# WindVane_1.net
KiCad netlist of a schematic drawn in EAGLE
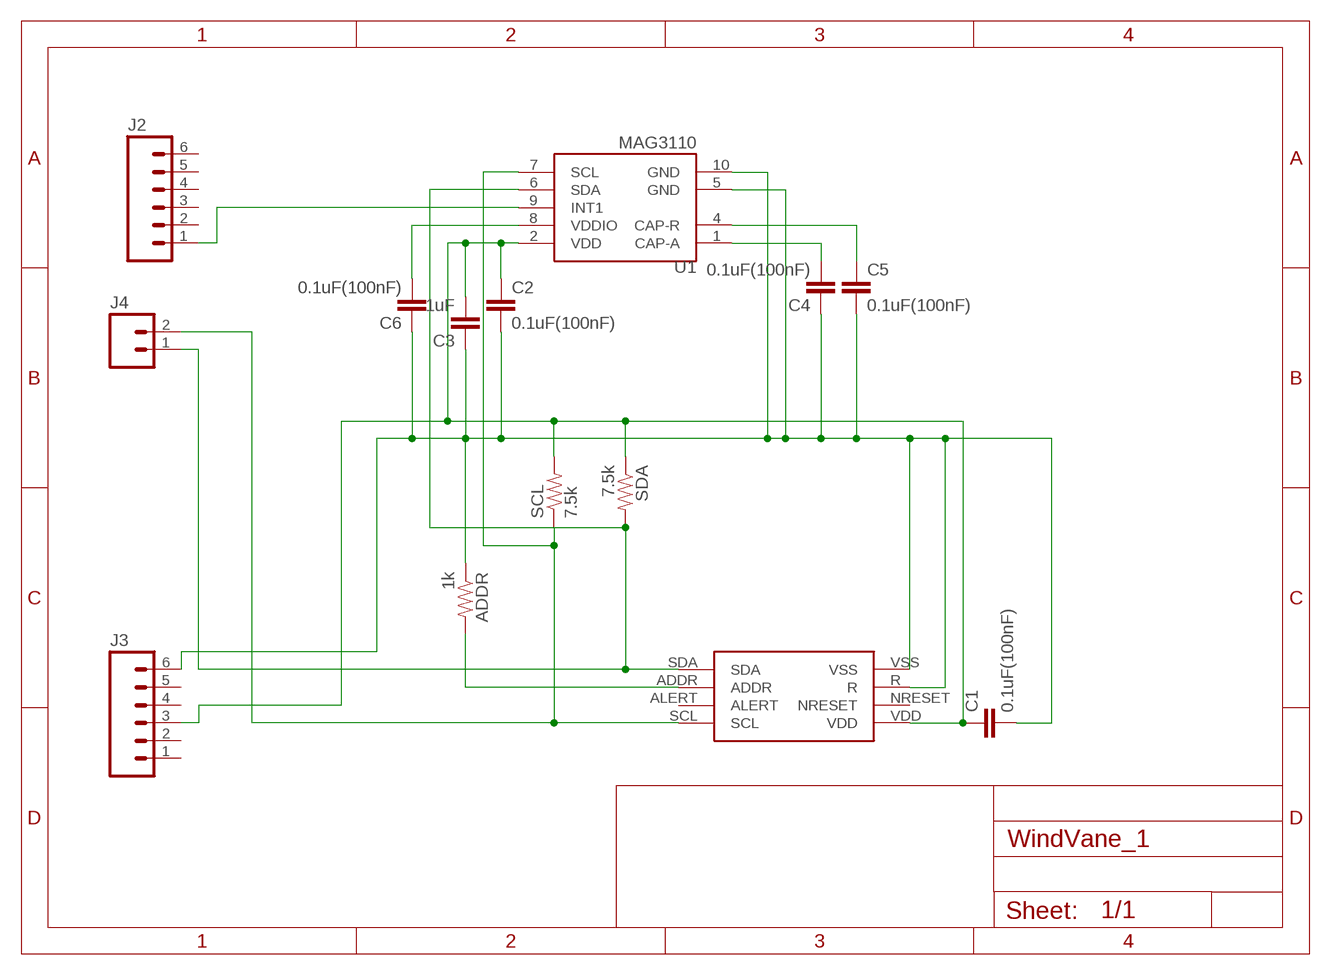
[diagram p0: schematic, sheet 1]

(export (version "E")
  (design (tool "Eeschema 10.0.6"))
  (components
    (comp (ref "ADDR")
      (value "1k")
      (footprint "eagle-import:1206")
      (libsource (lib "eagle-import") (part "RESISTOR1206"))
    )
    (comp (ref "C1")
      (value "0.1uF(100nF)")
      (footprint "eagle-import:0603-CAP")
      (libsource (lib "eagle-import") (part "SparkFun-Passives_CAP0603-CAP"))
    )
    (comp (ref "C2")
      (value "0.1uF(100nF)")
      (footprint "eagle-import:0603-CAP")
      (libsource (lib "eagle-import") (part "0.1UF-25V(+80/-20%)(0603)"))
    )
    (comp (ref "C3")
      (value "1uF")
      (footprint "eagle-import:0402-CAP")
      (libsource (lib "eagle-import") (part "CAP0402-CAP"))
    )
    (comp (ref "C4")
      (value "0.1uF(100nF)")
      (footprint "eagle-import:0603-CAP")
      (libsource (lib "eagle-import") (part "0.1UF-25V(+80/-20%)(0603)"))
    )
    (comp (ref "C5")
      (value "0.1uF(100nF)")
      (footprint "eagle-import:0603-CAP")
      (libsource (lib "eagle-import") (part "0.1UF-25V(+80/-20%)(0603)"))
    )
    (comp (ref "C6")
      (value "0.1uF(100nF)")
      (footprint "eagle-import:0603-CAP")
      (libsource (lib "eagle-import") (part "0.1UF-25V(+80/-20%)(0603)"))
    )
    (comp (ref "J2")
      (value "M06NO_SILK_YES_STOP")
      (footprint "eagle-import:1X06_NO_SILK_YES_STOP")
      (libsource (lib "eagle-import") (part "M06NO_SILK_YES_STOP"))
    )
    (comp (ref "J3")
      (value "M06NO_SILK_YES_STOP")
      (footprint "eagle-import:1X06_NO_SILK_YES_STOP")
      (libsource (lib "eagle-import") (part "M06NO_SILK_YES_STOP"))
    )
    (comp (ref "J4")
      (value "M02PTH")
      (footprint "eagle-import:1X02")
      (libsource (lib "eagle-import") (part "M02PTH"))
    )
    (comp (ref "SCL")
      (value "7.5k")
      (footprint "eagle-import:1206")
      (libsource (lib "eagle-import") (part "RESISTOR1206"))
    )
    (comp (ref "SDA")
      (value "7.5k")
      (footprint "eagle-import:1206")
      (libsource (lib "eagle-import") (part "RESISTOR1206"))
    )
    (comp (ref "U$1")
      (value "SHT3X-DISSURFACE_MOUNT")
      (footprint "eagle-import:SHT3X-DIS")
      (libsource (lib "eagle-import") (part "SHT3X-DISSURFACE_MOUNT"))
    )
    (comp (ref "U1")
      (value "MAG3110")
      (footprint "eagle-import:DFN-10")
      (libsource (lib "eagle-import") (part "MAG3110"))
    )
  )
  (nets
    (net (code "1") (name "Net-(ADDR-Pad1)") (class "Default")
      (node (ref "ADDR") (pin "1") (pinfunction "1_1") (pintype "passive"))
      (node (ref "C1") (pin "2") (pinfunction "2_2") (pintype "passive"))
      (node (ref "C2") (pin "2") (pinfunction "2_2") (pintype "passive"))
      (node (ref "C3") (pin "1") (pinfunction "1_1") (pintype "passive"))
      (node (ref "C4") (pin "1") (pinfunction "1_1") (pintype "passive"))
      (node (ref "C5") (pin "2") (pinfunction "2_2") (pintype "passive"))
      (node (ref "C6") (pin "1") (pinfunction "1_1") (pintype "passive"))
      (node (ref "J3") (pin "6") (pinfunction "6_6") (pintype "passive"))
      (node (ref "U$1") (pin "R") (pinfunction "R_R") (pintype "bidirectional"))
      (node (ref "U$1") (pin "VSS") (pinfunction "VSS_VSS") (pintype "bidirectional"))
      (node (ref "U1") (pin "10") (pinfunction "GND_10") (pintype "bidirectional"))
      (node (ref "U1") (pin "5") (pinfunction "GND_5") (pintype "bidirectional"))
    )
    (net (code "2") (name "Net-(ADDR-Pad2)") (class "Default")
      (node (ref "ADDR") (pin "2") (pinfunction "2_2") (pintype "passive"))
      (node (ref "U$1") (pin "ADDR") (pinfunction "ADDR_ADDR") (pintype "bidirectional"))
    )
    (net (code "3") (name "Net-(U1-CAP-A)") (class "Default")
      (node (ref "C4") (pin "2") (pinfunction "2_2") (pintype "passive"))
      (node (ref "U1") (pin "1") (pinfunction "CAP-A_1") (pintype "bidirectional"))
    )
    (net (code "4") (name "Net-(U1-CAP-R)") (class "Default")
      (node (ref "C5") (pin "1") (pinfunction "1_1") (pintype "passive"))
      (node (ref "U1") (pin "4") (pinfunction "CAP-R_4") (pintype "bidirectional"))
    )
    (net (code "5") (name "Net-(U1-INT1)") (class "Default")
      (node (ref "J2") (pin "1") (pinfunction "1_1") (pintype "passive"))
      (node (ref "U1") (pin "9") (pinfunction "INT1_9") (pintype "bidirectional"))
    )
    (net (code "6") (name "Net-(U1-SCL)") (class "Default")
      (node (ref "J4") (pin "2") (pinfunction "2_2") (pintype "passive"))
      (node (ref "SCL") (pin "1") (pinfunction "1_1") (pintype "passive"))
      (node (ref "U$1") (pin "SCL") (pinfunction "SCL_SCL") (pintype "bidirectional"))
      (node (ref "U1") (pin "7") (pinfunction "SCL_7") (pintype "bidirectional"))
    )
    (net (code "7") (name "Net-(U1-SDA)") (class "Default")
      (node (ref "J4") (pin "1") (pinfunction "1_1") (pintype "passive"))
      (node (ref "SDA") (pin "2") (pinfunction "2_2") (pintype "passive"))
      (node (ref "U$1") (pin "SDA") (pinfunction "SDA_SDA") (pintype "bidirectional"))
      (node (ref "U1") (pin "6") (pinfunction "SDA_6") (pintype "bidirectional"))
    )
    (net (code "8") (name "Net-(U1-VDD)") (class "Default")
      (node (ref "C1") (pin "1") (pinfunction "1_1") (pintype "passive"))
      (node (ref "C2") (pin "1") (pinfunction "1_1") (pintype "passive"))
      (node (ref "C3") (pin "2") (pinfunction "2_2") (pintype "passive"))
      (node (ref "J3") (pin "3") (pinfunction "3_3") (pintype "passive"))
      (node (ref "SCL") (pin "2") (pinfunction "2_2") (pintype "passive"))
      (node (ref "SDA") (pin "1") (pinfunction "1_1") (pintype "passive"))
      (node (ref "U$1") (pin "VDD") (pinfunction "VDD_VDD") (pintype "bidirectional"))
      (node (ref "U1") (pin "2") (pinfunction "VDD_2") (pintype "bidirectional"))
    )
    (net (code "9") (name "Net-(U1-VDDIO)") (class "Default")
      (node (ref "C6") (pin "2") (pinfunction "2_2") (pintype "passive"))
      (node (ref "U1") (pin "8") (pinfunction "VDDIO_8") (pintype "bidirectional"))
    )
    (net (code "10") (name "unconnected-(J2-Pad2)") (class "Default")
      (node (ref "J2") (pin "2") (pinfunction "2_2") (pintype "passive"))
    )
    (net (code "11") (name "unconnected-(J2-Pad3)") (class "Default")
      (node (ref "J2") (pin "3") (pinfunction "3_3") (pintype "passive"))
    )
    (net (code "12") (name "unconnected-(J2-Pad4)") (class "Default")
      (node (ref "J2") (pin "4") (pinfunction "4_4") (pintype "passive"))
    )
    (net (code "13") (name "unconnected-(J2-Pad5)") (class "Default")
      (node (ref "J2") (pin "5") (pinfunction "5_5") (pintype "passive"))
    )
    (net (code "14") (name "unconnected-(J2-Pad6)") (class "Default")
      (node (ref "J2") (pin "6") (pinfunction "6_6") (pintype "passive"))
    )
    (net (code "15") (name "unconnected-(J3-Pad1)") (class "Default")
      (node (ref "J3") (pin "1") (pinfunction "1_1") (pintype "passive"))
    )
    (net (code "16") (name "unconnected-(J3-Pad2)") (class "Default")
      (node (ref "J3") (pin "2") (pinfunction "2_2") (pintype "passive"))
    )
    (net (code "17") (name "unconnected-(J3-Pad4)") (class "Default")
      (node (ref "J3") (pin "4") (pinfunction "4_4") (pintype "passive"))
    )
    (net (code "18") (name "unconnected-(J3-Pad5)") (class "Default")
      (node (ref "J3") (pin "5") (pinfunction "5_5") (pintype "passive"))
    )
    (net (code "19") (name "unconnected-(U$1-PadALERT)") (class "Default")
      (node (ref "U$1") (pin "ALERT") (pinfunction "ALERT_ALERT") (pintype "bidirectional"))
    )
    (net (code "20") (name "unconnected-(U$1-PadNRESET)") (class "Default")
      (node (ref "U$1") (pin "NRESET") (pinfunction "NRESET_NRESET") (pintype "bidirectional"))
    )
  )
)
